# 2228_Recepteur_MIKROE_NRF.net
KiCad netlist of a schematic drawn in Altium Designer
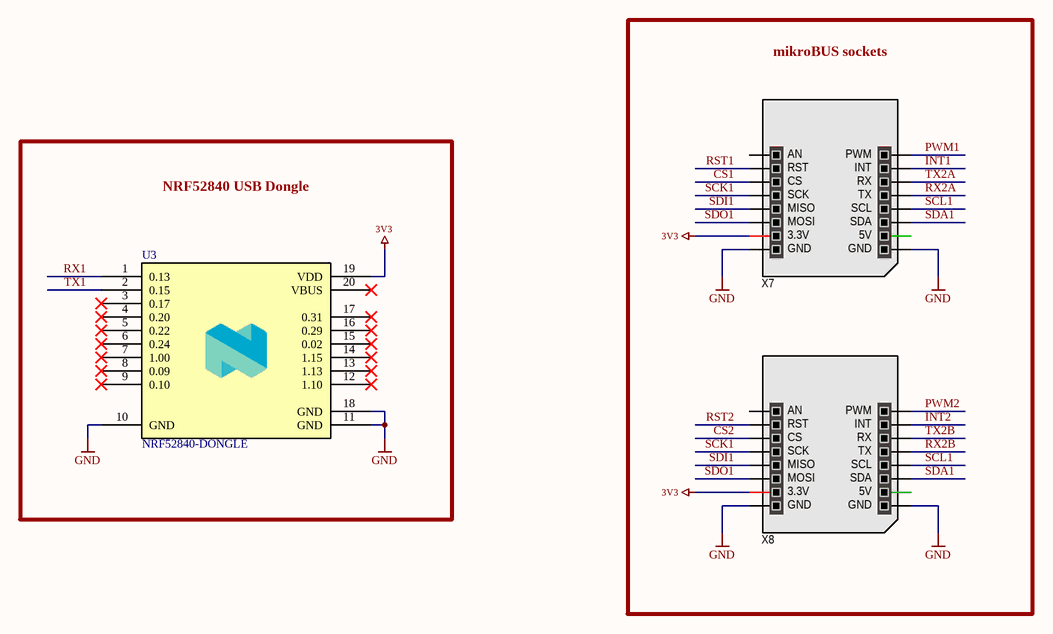
[diagram p0: 2228_Recepteur_MIKROE_NRF.SchDoc]

(export (version "E")
  (design (tool "Eeschema 10.0.6"))
  (components
    (comp (ref "U3")
      (value "NRF52840-DONGLE")
      (footprint "NRF52840_DONGLE")
      (fields (field (name "MANUFACTURER") "Nordic Semiconductor"))
      (libsource (lib "2228_AlarmeFenetre_Symbols") (part "NRF52840-DONGLE"))
    )
    (comp (ref "X7")
      (value "MIKROBUS HOST CONN TH 16")
      (footprint "MIKROBUS HOST CONN. TH")
      (libsource (lib "2228_AlarmeFenetre_Symbols") (part "MIKROBUS HOST CONN"))
    )
    (comp (ref "X8")
      (value "MIKROBUS HOST CONN TH 16")
      (footprint "MIKROBUS HOST CONN. TH")
      (libsource (lib "2228_AlarmeFenetre_Symbols") (part "MIKROBUS HOST CONN"))
    )
  )
  (nets
    (net (code "1") (name "/CS1") (class "Default")
      (node (ref "X7") (pin "3") (pinfunction "CS_3") (pintype "passive"))
    )
    (net (code "2") (name "/CS2") (class "Default")
      (node (ref "X8") (pin "3") (pinfunction "CS_3") (pintype "passive"))
    )
    (net (code "3") (name "/INT1") (class "Default")
      (node (ref "X7") (pin "15") (pinfunction "INT_15") (pintype "passive"))
    )
    (net (code "4") (name "/INT2") (class "Default")
      (node (ref "X8") (pin "15") (pinfunction "INT_15") (pintype "passive"))
    )
    (net (code "5") (name "/PWM1") (class "Default")
      (node (ref "X7") (pin "16") (pinfunction "PWM_16") (pintype "passive"))
    )
    (net (code "6") (name "/PWM2") (class "Default")
      (node (ref "X8") (pin "16") (pinfunction "PWM_16") (pintype "passive"))
    )
    (net (code "7") (name "/RST1") (class "Default")
      (node (ref "X7") (pin "2") (pinfunction "RST_2") (pintype "passive"))
    )
    (net (code "8") (name "/RST2") (class "Default")
      (node (ref "X8") (pin "2") (pinfunction "RST_2") (pintype "passive"))
    )
    (net (code "9") (name "/RX1") (class "Default")
      (node (ref "U3") (pin "1") (pinfunction "0.13_1") (pintype "passive"))
    )
    (net (code "10") (name "/RX2A") (class "Default")
      (node (ref "X7") (pin "13") (pinfunction "TX_13") (pintype "passive"))
    )
    (net (code "11") (name "/RX2B") (class "Default")
      (node (ref "X8") (pin "13") (pinfunction "TX_13") (pintype "passive"))
    )
    (net (code "12") (name "/SCK1") (class "Default")
      (node (ref "X7") (pin "4") (pinfunction "SCK_4") (pintype "passive"))
      (node (ref "X8") (pin "4") (pinfunction "SCK_4") (pintype "passive"))
    )
    (net (code "13") (name "/SCL1") (class "Default")
      (node (ref "X7") (pin "12") (pinfunction "SCL_12") (pintype "passive"))
      (node (ref "X8") (pin "12") (pinfunction "SCL_12") (pintype "passive"))
    )
    (net (code "14") (name "/SDA1") (class "Default")
      (node (ref "X7") (pin "11") (pinfunction "SDA_11") (pintype "passive"))
      (node (ref "X8") (pin "11") (pinfunction "SDA_11") (pintype "passive"))
    )
    (net (code "15") (name "/SDI1") (class "Default")
      (node (ref "X7") (pin "5") (pinfunction "MISO_5") (pintype "passive"))
      (node (ref "X8") (pin "5") (pinfunction "MISO_5") (pintype "passive"))
    )
    (net (code "16") (name "/SDO1") (class "Default")
      (node (ref "X7") (pin "6") (pinfunction "MOSI_6") (pintype "passive"))
      (node (ref "X8") (pin "6") (pinfunction "MOSI_6") (pintype "passive"))
    )
    (net (code "17") (name "/TX1") (class "Default")
      (node (ref "U3") (pin "2") (pinfunction "0.15_2") (pintype "passive"))
    )
    (net (code "18") (name "/TX2A") (class "Default")
      (node (ref "X7") (pin "14") (pinfunction "RX_14") (pintype "passive"))
    )
    (net (code "19") (name "/TX2B") (class "Default")
      (node (ref "X8") (pin "14") (pinfunction "RX_14") (pintype "passive"))
    )
    (net (code "20") (name "3V3") (class "Default")
      (node (ref "U3") (pin "19") (pinfunction "VDD_19") (pintype "passive"))
      (node (ref "X7") (pin "7") (pinfunction "3.3V_7") (pintype "passive"))
      (node (ref "X8") (pin "7") (pinfunction "3.3V_7") (pintype "passive"))
    )
    (net (code "21") (name "GND") (class "Default")
      (node (ref "U3") (pin "10") (pinfunction "GND_10") (pintype "passive"))
      (node (ref "U3") (pin "11") (pinfunction "GND_11") (pintype "passive"))
      (node (ref "U3") (pin "18") (pinfunction "GND_18") (pintype "passive"))
      (node (ref "X7") (pin "8") (pinfunction "GND_8") (pintype "passive"))
      (node (ref "X7") (pin "9") (pinfunction "GND_9") (pintype "passive"))
      (node (ref "X8") (pin "8") (pinfunction "GND_8") (pintype "passive"))
      (node (ref "X8") (pin "9") (pinfunction "GND_9") (pintype "passive"))
    )
    (net (code "22") (name "unconnected-(U3-0.02-Pad15)") (class "Default")
      (node (ref "U3") (pin "15") (pinfunction "0.02_15") (pintype "passive+no_connect"))
    )
    (net (code "23") (name "unconnected-(U3-0.09-Pad8)") (class "Default")
      (node (ref "U3") (pin "8") (pinfunction "0.09_8") (pintype "passive+no_connect"))
    )
    (net (code "24") (name "unconnected-(U3-0.10-Pad9)") (class "Default")
      (node (ref "U3") (pin "9") (pinfunction "0.10_9") (pintype "passive+no_connect"))
    )
    (net (code "25") (name "unconnected-(U3-0.17-Pad3)") (class "Default")
      (node (ref "U3") (pin "3") (pinfunction "0.17_3") (pintype "passive+no_connect"))
    )
    (net (code "26") (name "unconnected-(U3-0.20-Pad4)") (class "Default")
      (node (ref "U3") (pin "4") (pinfunction "0.20_4") (pintype "passive+no_connect"))
    )
    (net (code "27") (name "unconnected-(U3-0.22-Pad5)") (class "Default")
      (node (ref "U3") (pin "5") (pinfunction "0.22_5") (pintype "passive+no_connect"))
    )
    (net (code "28") (name "unconnected-(U3-0.24-Pad6)") (class "Default")
      (node (ref "U3") (pin "6") (pinfunction "0.24_6") (pintype "passive+no_connect"))
    )
    (net (code "29") (name "unconnected-(U3-0.29-Pad16)") (class "Default")
      (node (ref "U3") (pin "16") (pinfunction "0.29_16") (pintype "passive+no_connect"))
    )
    (net (code "30") (name "unconnected-(U3-0.31-Pad17)") (class "Default")
      (node (ref "U3") (pin "17") (pinfunction "0.31_17") (pintype "passive+no_connect"))
    )
    (net (code "31") (name "unconnected-(U3-1.00-Pad7)") (class "Default")
      (node (ref "U3") (pin "7") (pinfunction "1.00_7") (pintype "passive+no_connect"))
    )
    (net (code "32") (name "unconnected-(U3-1.10-Pad12)") (class "Default")
      (node (ref "U3") (pin "12") (pinfunction "1.10_12") (pintype "passive+no_connect"))
    )
    (net (code "33") (name "unconnected-(U3-1.13-Pad13)") (class "Default")
      (node (ref "U3") (pin "13") (pinfunction "1.13_13") (pintype "passive+no_connect"))
    )
    (net (code "34") (name "unconnected-(U3-1.15-Pad14)") (class "Default")
      (node (ref "U3") (pin "14") (pinfunction "1.15_14") (pintype "passive+no_connect"))
    )
    (net (code "35") (name "unconnected-(U3-VBUS-Pad20)") (class "Default")
      (node (ref "U3") (pin "20") (pinfunction "VBUS_20") (pintype "passive+no_connect"))
    )
    (net (code "36") (name "unconnected-(X7-5V-Pad10)") (class "Default")
      (node (ref "X7") (pin "10") (pinfunction "5V_10") (pintype "passive"))
    )
    (net (code "37") (name "unconnected-(X7-AN-Pad1)") (class "Default")
      (node (ref "X7") (pin "1") (pinfunction "AN_1") (pintype "passive"))
    )
    (net (code "38") (name "unconnected-(X8-5V-Pad10)") (class "Default")
      (node (ref "X8") (pin "10") (pinfunction "5V_10") (pintype "passive"))
    )
    (net (code "39") (name "unconnected-(X8-AN-Pad1)") (class "Default")
      (node (ref "X8") (pin "1") (pinfunction "AN_1") (pintype "passive"))
    )
  )
)
